# 60x40-motor-controller-0_3.net
KiCad netlist of a schematic drawn in EAGLE
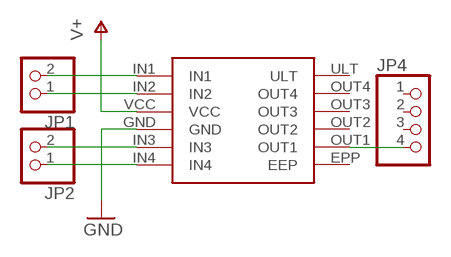
[diagram p0: schematic, sheet 1]
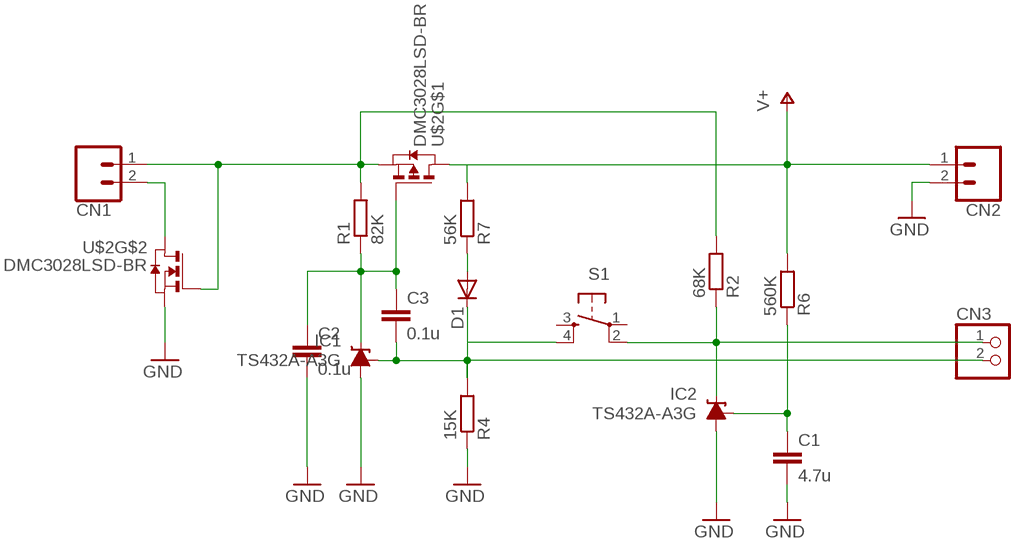
[diagram p1: schematic, sheet 2]

(export (version "E")
  (design (tool "Eeschema 10.0.6"))
  (components
    (comp (ref "C1")
      (value "4.7u")
      (footprint "eagle-import:C025-025X050")
      (libsource (lib "eagle-import") (part "C-EU025-025X050"))
    )
    (comp (ref "C2")
      (value "0.1u")
      (footprint "eagle-import:C025-024X044")
      (libsource (lib "eagle-import") (part "C-EU025-024X044"))
    )
    (comp (ref "C3")
      (value "0.1u")
      (footprint "eagle-import:C025-024X044")
      (libsource (lib "eagle-import") (part "C-EU025-024X044"))
    )
    (comp (ref "CN1")
      (value "CONN_02-JST-XTH")
      (footprint "eagle-import:JST-2-XTH")
      (libsource (lib "eagle-import") (part "CONN_02-JST-XTH"))
    )
    (comp (ref "CN2")
      (value "CONN_02-JST-XTH")
      (footprint "eagle-import:JST-2-XTH")
      (libsource (lib "eagle-import") (part "CONN_02-JST-XTH"))
    )
    (comp (ref "CN3")
      (value "PINHD-1X2/90")
      (footprint "eagle-import:1X02_90")
      (libsource (lib "eagle-import") (part "PINHD-1X2/90"))
    )
    (comp (ref "D1")
      (value "DIODE-D-5")
      (footprint "eagle-import:D-5")
      (libsource (lib "eagle-import") (part "DIODE-D-5"))
    )
    (comp (ref "IC1")
      (value "TS432A-A3G")
      (footprint "eagle-import:TO92-LINE")
      (libsource (lib "eagle-import") (part "TS432A-A3G"))
    )
    (comp (ref "IC2")
      (value "TS432A-A3G")
      (footprint "eagle-import:TO92-LINE")
      (libsource (lib "eagle-import") (part "TS432A-A3G"))
    )
    (comp (ref "R1")
      (value "82K")
      (footprint "eagle-import:0204V")
      (libsource (lib "eagle-import") (part "R-EU_0204/2V"))
    )
    (comp (ref "R2")
      (value "68K")
      (footprint "eagle-import:0204_7")
      (libsource (lib "eagle-import") (part "R-EU_0204/7"))
    )
    (comp (ref "R4")
      (value "15K")
      (footprint "eagle-import:0204V")
      (libsource (lib "eagle-import") (part "R-EU_0204/2V"))
    )
    (comp (ref "R6")
      (value "560K")
      (footprint "eagle-import:0207_10")
      (libsource (lib "eagle-import") (part "R-EU_0207/10"))
    )
    (comp (ref "R7")
      (value "56K")
      (footprint "eagle-import:0204V")
      (libsource (lib "eagle-import") (part "R-EU_0204/2V"))
    )
    (comp (ref "S1")
      (value "PROTO-MICRO-SWITCH")
      (footprint "eagle-import:B3F-10XX-PROTO")
      (libsource (lib "eagle-import") (part "PROTO-MICRO-SWITCH"))
    )
    (comp (ref "U$2")
      (value "DMC3028LSD-BR")
      (footprint "eagle-import:DIL8-BREAKOUT")
      (libsource (lib "eagle-import") (part "DMC3028LSD-BR"))
    )
    (comp (ref "JP1")
      (value "PINHD-1X2/90")
      (footprint "eagle-import:1X02_90")
      (libsource (lib "eagle-import") (part "PINHD-1X2/90"))
    )
    (comp (ref "JP2")
      (value "PINHD-1X2/90")
      (footprint "eagle-import:1X02_90")
      (libsource (lib "eagle-import") (part "PINHD-1X2/90"))
    )
    (comp (ref "JP4")
      (value "PINHD-1X4/90")
      (footprint "eagle-import:1X04_90")
      (libsource (lib "eagle-import") (part "PINHD-1X4/90"))
    )
    (comp (ref "U$1")
      (value "DRV8833-MODULE")
      (footprint "eagle-import:DRV8833-BRKOUT")
      (libsource (lib "eagle-import") (part "DRV8833-MODULE"))
    )
  )
  (nets
    (net (code "1") (name "GND") (class "Default")
      (node (ref "C1") (pin "2") (pinfunction "2_2") (pintype "passive"))
      (node (ref "C2") (pin "2") (pinfunction "2_2") (pintype "passive"))
      (node (ref "CN2") (pin "2") (pinfunction "2_2") (pintype "passive"))
      (node (ref "IC1") (pin "2") (pinfunction "A_2") (pintype "passive"))
      (node (ref "IC2") (pin "2") (pinfunction "A_2") (pintype "passive"))
      (node (ref "R4") (pin "1") (pinfunction "1_1") (pintype "passive"))
      (node (ref "U$1") (pin "GND") (pinfunction "GND_GND") (pintype "bidirectional"))
      (node (ref "U$2") (pin "1") (pinfunction "S_1") (pintype "passive"))
    )
    (net (code "2") (name "Net-(CN1-Pad2)") (class "Default")
      (node (ref "CN1") (pin "2") (pinfunction "2_2") (pintype "passive"))
      (node (ref "U$2") (pin "7") (pinfunction "D_7") (pintype "passive"))
      (node (ref "U$2") (pin "8") (pinfunction "D_8") (pintype "passive"))
    )
    (net (code "3") (name "Net-(D1-PadA)") (class "Default")
      (node (ref "D1") (pin "A") (pinfunction "A_A") (pintype "passive"))
      (node (ref "R7") (pin "1") (pinfunction "1_1") (pintype "passive"))
    )
    (net (code "4") (name "Net-(IC1-C)") (class "Default")
      (node (ref "C2") (pin "1") (pinfunction "1_1") (pintype "passive"))
      (node (ref "C3") (pin "1") (pinfunction "1_1") (pintype "passive"))
      (node (ref "IC1") (pin "1") (pinfunction "C_1") (pintype "passive"))
      (node (ref "R1") (pin "1") (pinfunction "1_1") (pintype "passive"))
      (node (ref "U$2") (pin "4") (pinfunction "G_4") (pintype "passive"))
    )
    (net (code "5") (name "Net-(IC1-FB)") (class "Default")
      (node (ref "C3") (pin "2") (pinfunction "2_2") (pintype "passive"))
      (node (ref "CN3") (pin "2") (pinfunction "2_2") (pintype "passive"))
      (node (ref "D1") (pin "C") (pinfunction "C_C") (pintype "passive"))
      (node (ref "IC1") (pin "3") (pinfunction "FB_3") (pintype "passive"))
      (node (ref "R4") (pin "2") (pinfunction "2_2") (pintype "passive"))
      (node (ref "S1") (pin "4") (pinfunction "S1_4") (pintype "passive"))
    )
    (net (code "6") (name "Net-(IC2-C)") (class "Default")
      (node (ref "CN3") (pin "1") (pinfunction "1_1") (pintype "passive"))
      (node (ref "IC2") (pin "1") (pinfunction "C_1") (pintype "passive"))
      (node (ref "R2") (pin "1") (pinfunction "1_1") (pintype "passive"))
      (node (ref "S1") (pin "2") (pinfunction "P1_2") (pintype "passive"))
    )
    (net (code "7") (name "Net-(IC2-FB)") (class "Default")
      (node (ref "C1") (pin "1") (pinfunction "1_1") (pintype "passive"))
      (node (ref "IC2") (pin "3") (pinfunction "FB_3") (pintype "passive"))
      (node (ref "R6") (pin "1") (pinfunction "1_1") (pintype "passive"))
    )
    (net (code "8") (name "Net-(JP1-Pad1)") (class "Default")
      (node (ref "JP1") (pin "1") (pinfunction "1_1") (pintype "passive"))
      (node (ref "U$1") (pin "IN2") (pinfunction "IN2_IN2") (pintype "bidirectional"))
    )
    (net (code "9") (name "Net-(JP1-Pad2)") (class "Default")
      (node (ref "JP1") (pin "2") (pinfunction "2_2") (pintype "passive"))
      (node (ref "U$1") (pin "IN1") (pinfunction "IN1_IN1") (pintype "bidirectional"))
    )
    (net (code "10") (name "Net-(JP2-Pad1)") (class "Default")
      (node (ref "JP2") (pin "1") (pinfunction "1_1") (pintype "passive"))
      (node (ref "U$1") (pin "IN4") (pinfunction "IN4_IN4") (pintype "bidirectional"))
    )
    (net (code "11") (name "Net-(JP2-Pad2)") (class "Default")
      (node (ref "JP2") (pin "2") (pinfunction "2_2") (pintype "passive"))
      (node (ref "U$1") (pin "IN3") (pinfunction "IN3_IN3") (pintype "bidirectional"))
    )
    (net (code "12") (name "Net-(JP4-Pad4)") (class "Default")
      (node (ref "JP4") (pin "4") (pinfunction "4_4") (pintype "passive"))
      (node (ref "U$1") (pin "OUT1") (pinfunction "OUT1_OUT1") (pintype "bidirectional"))
    )
    (net (code "13") (name "Net-(U$2A-S)") (class "Default")
      (node (ref "CN1") (pin "1") (pinfunction "1_1") (pintype "passive"))
      (node (ref "R1") (pin "2") (pinfunction "2_2") (pintype "passive"))
      (node (ref "R2") (pin "2") (pinfunction "2_2") (pintype "passive"))
      (node (ref "U$2") (pin "2") (pinfunction "G_2") (pintype "passive"))
      (node (ref "U$2") (pin "3") (pinfunction "S_3") (pintype "passive"))
    )
    (net (code "14") (name "V+") (class "Default")
      (node (ref "CN2") (pin "1") (pinfunction "1_1") (pintype "passive"))
      (node (ref "R6") (pin "2") (pinfunction "2_2") (pintype "passive"))
      (node (ref "R7") (pin "2") (pinfunction "2_2") (pintype "passive"))
      (node (ref "U$1") (pin "VCC") (pinfunction "VCC_VCC") (pintype "bidirectional"))
      (node (ref "U$2") (pin "5") (pinfunction "D_5") (pintype "passive"))
      (node (ref "U$2") (pin "6") (pinfunction "D_6") (pintype "passive"))
    )
    (net (code "15") (name "unconnected-(JP4-Pad1)") (class "Default")
      (node (ref "JP4") (pin "1") (pinfunction "1_1") (pintype "passive"))
    )
    (net (code "16") (name "unconnected-(JP4-Pad2)") (class "Default")
      (node (ref "JP4") (pin "2") (pinfunction "2_2") (pintype "passive"))
    )
    (net (code "17") (name "unconnected-(JP4-Pad3)") (class "Default")
      (node (ref "JP4") (pin "3") (pinfunction "3_3") (pintype "passive"))
    )
    (net (code "18") (name "unconnected-(S1-P-Pad1)") (class "Default")
      (node (ref "S1") (pin "1") (pinfunction "P_1") (pintype "passive"))
    )
    (net (code "19") (name "unconnected-(S1-S-Pad3)") (class "Default")
      (node (ref "S1") (pin "3") (pinfunction "S_3") (pintype "passive"))
    )
    (net (code "20") (name "unconnected-(U$1-EEP-PadEPP)") (class "Default")
      (node (ref "U$1") (pin "EPP") (pinfunction "EEP_EPP") (pintype "bidirectional"))
    )
    (net (code "21") (name "unconnected-(U$1-PadOUT2)") (class "Default")
      (node (ref "U$1") (pin "OUT2") (pinfunction "OUT2_OUT2") (pintype "bidirectional"))
    )
    (net (code "22") (name "unconnected-(U$1-PadOUT3)") (class "Default")
      (node (ref "U$1") (pin "OUT3") (pinfunction "OUT3_OUT3") (pintype "bidirectional"))
    )
    (net (code "23") (name "unconnected-(U$1-PadOUT4)") (class "Default")
      (node (ref "U$1") (pin "OUT4") (pinfunction "OUT4_OUT4") (pintype "bidirectional"))
    )
    (net (code "24") (name "unconnected-(U$1-PadULT)") (class "Default")
      (node (ref "U$1") (pin "ULT") (pinfunction "ULT_ULT") (pintype "bidirectional"))
    )
  )
)
